# Snow_LanteRn.net
KiCad netlist of a schematic drawn in Altium Designer
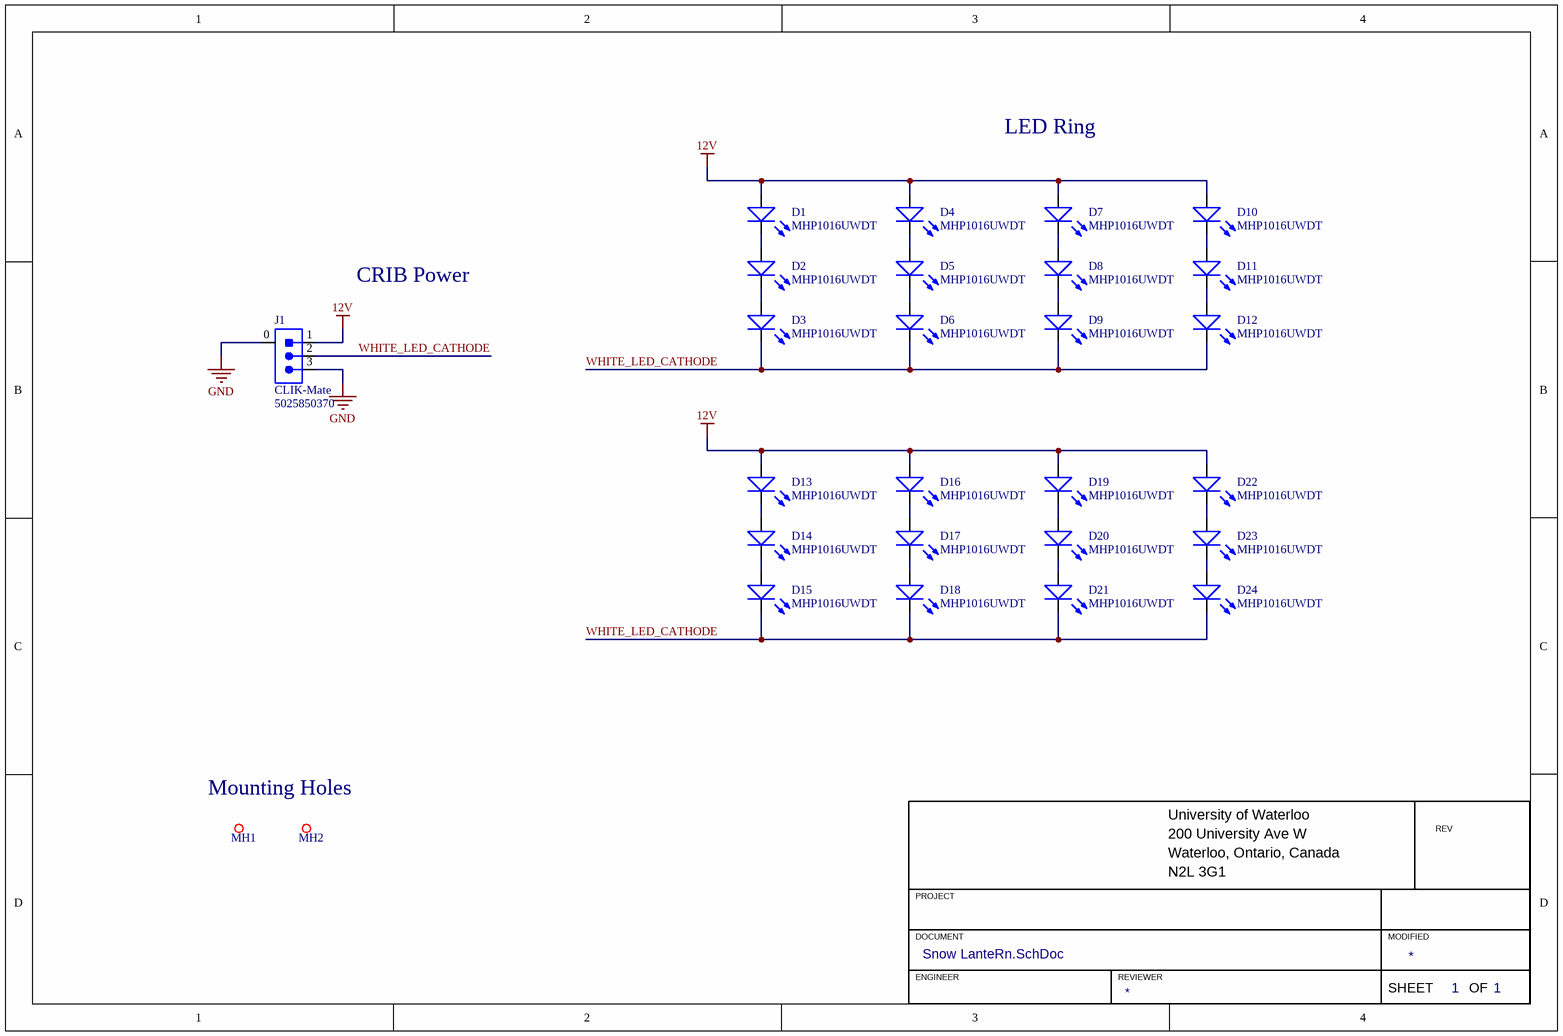
[diagram p0: Snow LanteRn.SchDoc]

(export (version "E")
  (design (tool "Eeschema 10.0.6"))
  (components
    (comp (ref "D1")
      (value "LED_WHITE_0603")
      (footprint "LED_0603")
      (description "LED WHITE FROSTED-LENS 0603 SMD")
      (fields (field (name "MANUFACTURER PART NUMBER 1") "MHP1016UWDT"))
      (libsource (lib "Personal_Schematic_Library_2022") (part "LED_WHITE_0603"))
    )
    (comp (ref "D2")
      (value "LED_WHITE_0603")
      (footprint "LED_0603")
      (description "LED WHITE FROSTED-LENS 0603 SMD")
      (fields (field (name "MANUFACTURER PART NUMBER 1") "MHP1016UWDT"))
      (libsource (lib "Personal_Schematic_Library_2022") (part "LED_WHITE_0603"))
    )
    (comp (ref "D3")
      (value "LED_WHITE_0603")
      (footprint "LED_0603")
      (description "LED WHITE FROSTED-LENS 0603 SMD")
      (fields (field (name "MANUFACTURER PART NUMBER 1") "MHP1016UWDT"))
      (libsource (lib "Personal_Schematic_Library_2022") (part "LED_WHITE_0603"))
    )
    (comp (ref "D4")
      (value "LED_WHITE_0603")
      (footprint "LED_0603")
      (description "LED WHITE FROSTED-LENS 0603 SMD")
      (fields (field (name "MANUFACTURER PART NUMBER 1") "MHP1016UWDT"))
      (libsource (lib "Personal_Schematic_Library_2022") (part "LED_WHITE_0603"))
    )
    (comp (ref "D5")
      (value "LED_WHITE_0603")
      (footprint "LED_0603")
      (description "LED WHITE FROSTED-LENS 0603 SMD")
      (fields (field (name "MANUFACTURER PART NUMBER 1") "MHP1016UWDT"))
      (libsource (lib "Personal_Schematic_Library_2022") (part "LED_WHITE_0603"))
    )
    (comp (ref "D6")
      (value "LED_WHITE_0603")
      (footprint "LED_0603")
      (description "LED WHITE FROSTED-LENS 0603 SMD")
      (fields (field (name "MANUFACTURER PART NUMBER 1") "MHP1016UWDT"))
      (libsource (lib "Personal_Schematic_Library_2022") (part "LED_WHITE_0603"))
    )
    (comp (ref "D7")
      (value "LED_WHITE_0603")
      (footprint "LED_0603")
      (description "LED WHITE FROSTED-LENS 0603 SMD")
      (fields (field (name "MANUFACTURER PART NUMBER 1") "MHP1016UWDT"))
      (libsource (lib "Personal_Schematic_Library_2022") (part "LED_WHITE_0603"))
    )
    (comp (ref "D8")
      (value "LED_WHITE_0603")
      (footprint "LED_0603")
      (description "LED WHITE FROSTED-LENS 0603 SMD")
      (fields (field (name "MANUFACTURER PART NUMBER 1") "MHP1016UWDT"))
      (libsource (lib "Personal_Schematic_Library_2022") (part "LED_WHITE_0603"))
    )
    (comp (ref "D9")
      (value "LED_WHITE_0603")
      (footprint "LED_0603")
      (description "LED WHITE FROSTED-LENS 0603 SMD")
      (fields (field (name "MANUFACTURER PART NUMBER 1") "MHP1016UWDT"))
      (libsource (lib "Personal_Schematic_Library_2022") (part "LED_WHITE_0603"))
    )
    (comp (ref "D10")
      (value "LED_WHITE_0603")
      (footprint "LED_0603")
      (description "LED WHITE FROSTED-LENS 0603 SMD")
      (fields (field (name "MANUFACTURER PART NUMBER 1") "MHP1016UWDT"))
      (libsource (lib "Personal_Schematic_Library_2022") (part "LED_WHITE_0603"))
    )
    (comp (ref "D11")
      (value "LED_WHITE_0603")
      (footprint "LED_0603")
      (description "LED WHITE FROSTED-LENS 0603 SMD")
      (fields (field (name "MANUFACTURER PART NUMBER 1") "MHP1016UWDT"))
      (libsource (lib "Personal_Schematic_Library_2022") (part "LED_WHITE_0603"))
    )
    (comp (ref "D12")
      (value "LED_WHITE_0603")
      (footprint "LED_0603")
      (description "LED WHITE FROSTED-LENS 0603 SMD")
      (fields (field (name "MANUFACTURER PART NUMBER 1") "MHP1016UWDT"))
      (libsource (lib "Personal_Schematic_Library_2022") (part "LED_WHITE_0603"))
    )
    (comp (ref "D13")
      (value "LED_WHITE_0603")
      (footprint "LED_0603")
      (description "LED WHITE FROSTED-LENS 0603 SMD")
      (fields (field (name "MANUFACTURER PART NUMBER 1") "MHP1016UWDT"))
      (libsource (lib "Personal_Schematic_Library_2022") (part "LED_WHITE_0603"))
    )
    (comp (ref "D14")
      (value "LED_WHITE_0603")
      (footprint "LED_0603")
      (description "LED WHITE FROSTED-LENS 0603 SMD")
      (fields (field (name "MANUFACTURER PART NUMBER 1") "MHP1016UWDT"))
      (libsource (lib "Personal_Schematic_Library_2022") (part "LED_WHITE_0603"))
    )
    (comp (ref "D15")
      (value "LED_WHITE_0603")
      (footprint "LED_0603")
      (description "LED WHITE FROSTED-LENS 0603 SMD")
      (fields (field (name "MANUFACTURER PART NUMBER 1") "MHP1016UWDT"))
      (libsource (lib "Personal_Schematic_Library_2022") (part "LED_WHITE_0603"))
    )
    (comp (ref "D16")
      (value "LED_WHITE_0603")
      (footprint "LED_0603")
      (description "LED WHITE FROSTED-LENS 0603 SMD")
      (fields (field (name "MANUFACTURER PART NUMBER 1") "MHP1016UWDT"))
      (libsource (lib "Personal_Schematic_Library_2022") (part "LED_WHITE_0603"))
    )
    (comp (ref "D17")
      (value "LED_WHITE_0603")
      (footprint "LED_0603")
      (description "LED WHITE FROSTED-LENS 0603 SMD")
      (fields (field (name "MANUFACTURER PART NUMBER 1") "MHP1016UWDT"))
      (libsource (lib "Personal_Schematic_Library_2022") (part "LED_WHITE_0603"))
    )
    (comp (ref "D18")
      (value "LED_WHITE_0603")
      (footprint "LED_0603")
      (description "LED WHITE FROSTED-LENS 0603 SMD")
      (fields (field (name "MANUFACTURER PART NUMBER 1") "MHP1016UWDT"))
      (libsource (lib "Personal_Schematic_Library_2022") (part "LED_WHITE_0603"))
    )
    (comp (ref "D19")
      (value "LED_WHITE_0603")
      (footprint "LED_0603")
      (description "LED WHITE FROSTED-LENS 0603 SMD")
      (fields (field (name "MANUFACTURER PART NUMBER 1") "MHP1016UWDT"))
      (libsource (lib "Personal_Schematic_Library_2022") (part "LED_WHITE_0603"))
    )
    (comp (ref "D20")
      (value "LED_WHITE_0603")
      (footprint "LED_0603")
      (description "LED WHITE FROSTED-LENS 0603 SMD")
      (fields (field (name "MANUFACTURER PART NUMBER 1") "MHP1016UWDT"))
      (libsource (lib "Personal_Schematic_Library_2022") (part "LED_WHITE_0603"))
    )
    (comp (ref "D21")
      (value "LED_WHITE_0603")
      (footprint "LED_0603")
      (description "LED WHITE FROSTED-LENS 0603 SMD")
      (fields (field (name "MANUFACTURER PART NUMBER 1") "MHP1016UWDT"))
      (libsource (lib "Personal_Schematic_Library_2022") (part "LED_WHITE_0603"))
    )
    (comp (ref "D22")
      (value "LED_WHITE_0603")
      (footprint "LED_0603")
      (description "LED WHITE FROSTED-LENS 0603 SMD")
      (fields (field (name "MANUFACTURER PART NUMBER 1") "MHP1016UWDT"))
      (libsource (lib "Personal_Schematic_Library_2022") (part "LED_WHITE_0603"))
    )
    (comp (ref "D23")
      (value "LED_WHITE_0603")
      (footprint "LED_0603")
      (description "LED WHITE FROSTED-LENS 0603 SMD")
      (fields (field (name "MANUFACTURER PART NUMBER 1") "MHP1016UWDT"))
      (libsource (lib "Personal_Schematic_Library_2022") (part "LED_WHITE_0603"))
    )
    (comp (ref "D24")
      (value "LED_WHITE_0603")
      (footprint "LED_0603")
      (description "LED WHITE FROSTED-LENS 0603 SMD")
      (fields (field (name "MANUFACTURER PART NUMBER 1") "MHP1016UWDT"))
      (libsource (lib "Personal_Schematic_Library_2022") (part "LED_WHITE_0603"))
    )
    (comp (ref "J1")
      (value "CON_3M_SM_RA")
      (footprint "MOLEX-5025850370")
      (description "CONN RCPT 3POS 0.059 TIN SMD R/A")
      (fields (field (name "FAMILY") "CLIK-Mate") (field (name "MANUFACTURER PART NUMBER 1") "5025850370"))
      (libsource (lib "Personal_Schematic_Library_2022") (part "CON_3M_SM_RA"))
    )
    (comp (ref "MH1")
      (value "MOUNTING_HOLE_M3")
      (footprint "MOUNTING_HOLE_3mm")
      (libsource (lib "UWRT_Schematic_Library_2020") (part "MOUNTING_HOLE_M3"))
    )
    (comp (ref "MH2")
      (value "MOUNTING_HOLE_M3")
      (footprint "MOUNTING_HOLE_3mm")
      (libsource (lib "UWRT_Schematic_Library_2020") (part "MOUNTING_HOLE_M3"))
    )
  )
  (nets
    (net (code "1") (name "/WHITE_LED_CATHODE") (class "Default")
      (node (ref "D12") (pin "1") (pinfunction "K_1") (pintype "passive"))
      (node (ref "D15") (pin "1") (pinfunction "K_1") (pintype "passive"))
      (node (ref "D18") (pin "1") (pinfunction "K_1") (pintype "passive"))
      (node (ref "D21") (pin "1") (pinfunction "K_1") (pintype "passive"))
      (node (ref "D24") (pin "1") (pinfunction "K_1") (pintype "passive"))
      (node (ref "D3") (pin "1") (pinfunction "K_1") (pintype "passive"))
      (node (ref "D6") (pin "1") (pinfunction "K_1") (pintype "passive"))
      (node (ref "D9") (pin "1") (pinfunction "K_1") (pintype "passive"))
      (node (ref "J1") (pin "2") (pinfunction "2_2") (pintype "passive"))
    )
    (net (code "2") (name "12V") (class "Default")
      (node (ref "D1") (pin "2") (pinfunction "A_2") (pintype "passive"))
      (node (ref "D10") (pin "2") (pinfunction "A_2") (pintype "passive"))
      (node (ref "D13") (pin "2") (pinfunction "A_2") (pintype "passive"))
      (node (ref "D16") (pin "2") (pinfunction "A_2") (pintype "passive"))
      (node (ref "D19") (pin "2") (pinfunction "A_2") (pintype "passive"))
      (node (ref "D22") (pin "2") (pinfunction "A_2") (pintype "passive"))
      (node (ref "D4") (pin "2") (pinfunction "A_2") (pintype "passive"))
      (node (ref "D7") (pin "2") (pinfunction "A_2") (pintype "passive"))
      (node (ref "J1") (pin "1") (pinfunction "1_1") (pintype "passive"))
    )
    (net (code "3") (name "GND") (class "Default")
      (node (ref "J1") (pin "0") (pinfunction "0_0") (pintype "passive"))
      (node (ref "J1") (pin "3") (pinfunction "3_3") (pintype "passive"))
    )
    (net (code "4") (name "Net-(D1-K)") (class "Default")
      (node (ref "D1") (pin "1") (pinfunction "K_1") (pintype "passive"))
      (node (ref "D2") (pin "2") (pinfunction "A_2") (pintype "passive"))
    )
    (net (code "5") (name "Net-(D2-K)") (class "Default")
      (node (ref "D2") (pin "1") (pinfunction "K_1") (pintype "passive"))
      (node (ref "D3") (pin "2") (pinfunction "A_2") (pintype "passive"))
    )
    (net (code "6") (name "Net-(D4-K)") (class "Default")
      (node (ref "D4") (pin "1") (pinfunction "K_1") (pintype "passive"))
      (node (ref "D5") (pin "2") (pinfunction "A_2") (pintype "passive"))
    )
    (net (code "7") (name "Net-(D5-K)") (class "Default")
      (node (ref "D5") (pin "1") (pinfunction "K_1") (pintype "passive"))
      (node (ref "D6") (pin "2") (pinfunction "A_2") (pintype "passive"))
    )
    (net (code "8") (name "Net-(D7-K)") (class "Default")
      (node (ref "D7") (pin "1") (pinfunction "K_1") (pintype "passive"))
      (node (ref "D8") (pin "2") (pinfunction "A_2") (pintype "passive"))
    )
    (net (code "9") (name "Net-(D8-K)") (class "Default")
      (node (ref "D8") (pin "1") (pinfunction "K_1") (pintype "passive"))
      (node (ref "D9") (pin "2") (pinfunction "A_2") (pintype "passive"))
    )
    (net (code "10") (name "Net-(D10-K)") (class "Default")
      (node (ref "D10") (pin "1") (pinfunction "K_1") (pintype "passive"))
      (node (ref "D11") (pin "2") (pinfunction "A_2") (pintype "passive"))
    )
    (net (code "11") (name "Net-(D11-K)") (class "Default")
      (node (ref "D11") (pin "1") (pinfunction "K_1") (pintype "passive"))
      (node (ref "D12") (pin "2") (pinfunction "A_2") (pintype "passive"))
    )
    (net (code "12") (name "Net-(D13-K)") (class "Default")
      (node (ref "D13") (pin "1") (pinfunction "K_1") (pintype "passive"))
      (node (ref "D14") (pin "2") (pinfunction "A_2") (pintype "passive"))
    )
    (net (code "13") (name "Net-(D14-K)") (class "Default")
      (node (ref "D14") (pin "1") (pinfunction "K_1") (pintype "passive"))
      (node (ref "D15") (pin "2") (pinfunction "A_2") (pintype "passive"))
    )
    (net (code "14") (name "Net-(D16-K)") (class "Default")
      (node (ref "D16") (pin "1") (pinfunction "K_1") (pintype "passive"))
      (node (ref "D17") (pin "2") (pinfunction "A_2") (pintype "passive"))
    )
    (net (code "15") (name "Net-(D17-K)") (class "Default")
      (node (ref "D17") (pin "1") (pinfunction "K_1") (pintype "passive"))
      (node (ref "D18") (pin "2") (pinfunction "A_2") (pintype "passive"))
    )
    (net (code "16") (name "Net-(D19-K)") (class "Default")
      (node (ref "D19") (pin "1") (pinfunction "K_1") (pintype "passive"))
      (node (ref "D20") (pin "2") (pinfunction "A_2") (pintype "passive"))
    )
    (net (code "17") (name "Net-(D20-K)") (class "Default")
      (node (ref "D20") (pin "1") (pinfunction "K_1") (pintype "passive"))
      (node (ref "D21") (pin "2") (pinfunction "A_2") (pintype "passive"))
    )
    (net (code "18") (name "Net-(D22-K)") (class "Default")
      (node (ref "D22") (pin "1") (pinfunction "K_1") (pintype "passive"))
      (node (ref "D23") (pin "2") (pinfunction "A_2") (pintype "passive"))
    )
    (net (code "19") (name "Net-(D23-K)") (class "Default")
      (node (ref "D23") (pin "1") (pinfunction "K_1") (pintype "passive"))
      (node (ref "D24") (pin "2") (pinfunction "A_2") (pintype "passive"))
    )
  )
)
